# Fuente_v1.net
KiCad netlist of a schematic drawn in EAGLE
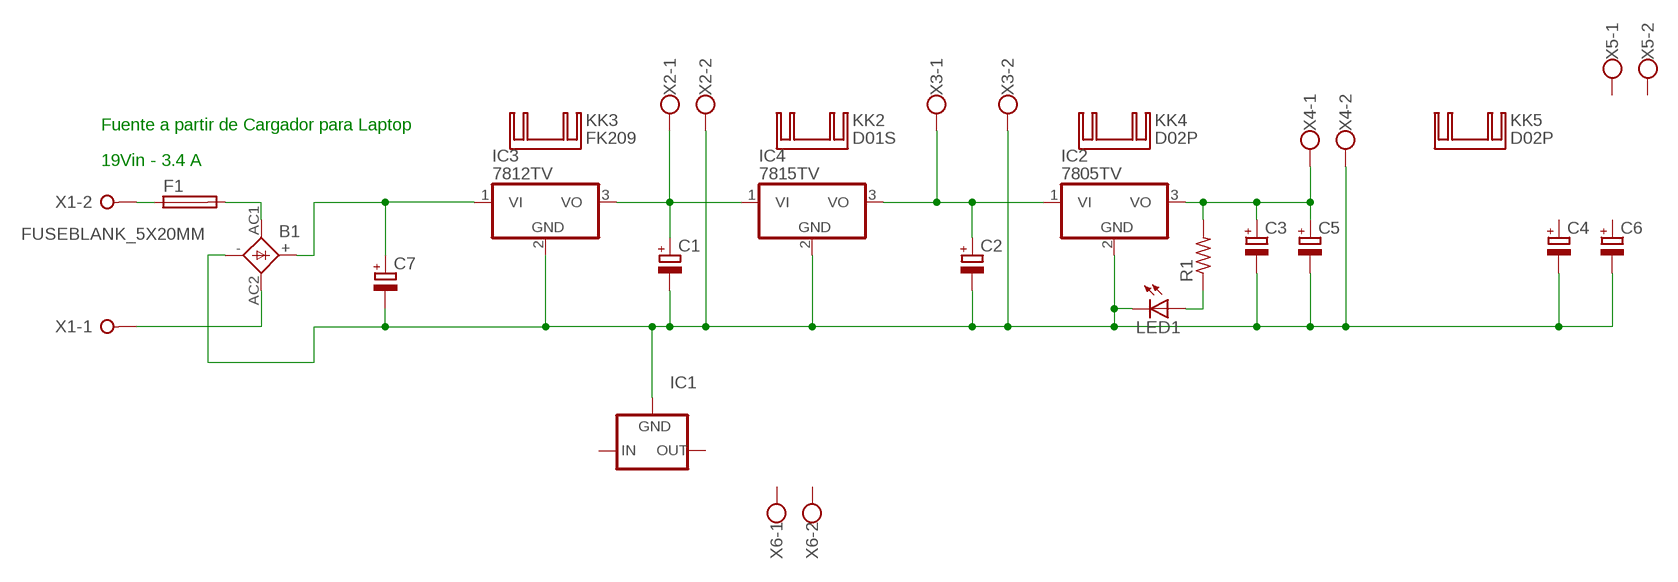
[diagram p0: schematic, sheet 1]

(export (version "E")
  (design (tool "Eeschema 10.0.6"))
  (components
    (comp (ref "B1")
      (value "FBM")
      (footprint "eagle-import:FBM")
      (libsource (lib "eagle-import") (part "FBM"))
    )
    (comp (ref "C1")
      (value "CPOL-EUE2.5-7")
      (footprint "eagle-import:E2,5-7")
      (libsource (lib "eagle-import") (part "CPOL-EUE2.5-7"))
    )
    (comp (ref "C2")
      (value "CPOL-EUE2.5-7")
      (footprint "eagle-import:E2,5-7")
      (libsource (lib "eagle-import") (part "CPOL-EUE2.5-7"))
    )
    (comp (ref "C3")
      (value "CPOL-EUE2.5-7")
      (footprint "eagle-import:E2,5-7")
      (libsource (lib "eagle-import") (part "CPOL-EUE2.5-7"))
    )
    (comp (ref "C4")
      (value "CPOL-EUE2.5-6")
      (footprint "eagle-import:E2,5-6")
      (libsource (lib "eagle-import") (part "CPOL-EUE2.5-6"))
    )
    (comp (ref "C5")
      (value "CPOL-EUE2.5-6")
      (footprint "eagle-import:E2,5-6")
      (libsource (lib "eagle-import") (part "CPOL-EUE2.5-6"))
    )
    (comp (ref "C6")
      (value "CPOL-EUE2.5-6")
      (footprint "eagle-import:E2,5-6")
      (libsource (lib "eagle-import") (part "CPOL-EUE2.5-6"))
    )
    (comp (ref "C7")
      (value "CPOL-EUE2.5-7")
      (footprint "eagle-import:E2,5-7")
      (libsource (lib "eagle-import") (part "CPOL-EUE2.5-7"))
    )
    (comp (ref "F1")
      (value "FUSEBLANK_5X20MM")
      (footprint "eagle-import:FUSE_HOLDER_5X20MM")
      (libsource (lib "eagle-import") (part "FUSEBLANK_5X20MM"))
    )
    (comp (ref "IC1")
      (value "79XX-TO3")
      (footprint "eagle-import:TO3-79")
      (libsource (lib "eagle-import") (part "79XX-TO3"))
    )
    (comp (ref "IC2")
      (value "7805TV")
      (footprint "eagle-import:TO220V")
      (libsource (lib "eagle-import") (part "78TV05"))
    )
    (comp (ref "IC3")
      (value "7812TV")
      (footprint "eagle-import:TO220V")
      (libsource (lib "eagle-import") (part "78TV12"))
    )
    (comp (ref "IC4")
      (value "7815TV")
      (footprint "eagle-import:TO220V")
      (libsource (lib "eagle-import") (part "78TV15"))
    )
    (comp (ref "KK2")
      (value "D01S")
      (footprint "eagle-import:D01S")
      (libsource (lib "eagle-import") (part "D01S"))
    )
    (comp (ref "KK3")
      (value "FK209")
      (footprint "eagle-import:FK209")
      (libsource (lib "eagle-import") (part "FK209"))
    )
    (comp (ref "KK4")
      (value "D02P")
      (footprint "eagle-import:D02PA")
      (libsource (lib "eagle-import") (part "D02P"))
    )
    (comp (ref "KK5")
      (value "D02P")
      (footprint "eagle-import:D02PA")
      (libsource (lib "eagle-import") (part "D02P"))
    )
    (comp (ref "LED1")
      (value "LED5MM")
      (footprint "eagle-import:LED5MM")
      (libsource (lib "eagle-import") (part "LED5MM"))
    )
    (comp (ref "R1")
      (value "R-US_0204/7")
      (footprint "eagle-import:0204_7")
      (libsource (lib "eagle-import") (part "R-US_0204/7"))
    )
    (comp (ref "X1")
      (value "W237-02P")
      (footprint "eagle-import:W237-132")
      (libsource (lib "eagle-import") (part "W237-02P"))
    )
    (comp (ref "X2")
      (value "W237-102")
      (footprint "eagle-import:W237-102")
      (fields (field (name "MPN") "237-102"))
      (libsource (lib "eagle-import") (part "W237-102"))
    )
    (comp (ref "X3")
      (value "W237-102")
      (footprint "eagle-import:W237-102")
      (fields (field (name "MPN") "237-102"))
      (libsource (lib "eagle-import") (part "W237-102"))
    )
    (comp (ref "X4")
      (value "W237-102")
      (footprint "eagle-import:W237-102")
      (fields (field (name "MPN") "237-102"))
      (libsource (lib "eagle-import") (part "W237-102"))
    )
    (comp (ref "X5")
      (value "W237-102")
      (footprint "eagle-import:W237-102")
      (fields (field (name "MPN") "237-102"))
      (libsource (lib "eagle-import") (part "W237-102"))
    )
    (comp (ref "X6")
      (value "W237-102")
      (footprint "eagle-import:W237-102")
      (fields (field (name "MPN") "237-102"))
      (libsource (lib "eagle-import") (part "W237-102"))
    )
  )
  (nets
    (net (code "1") (name "Net-(B1-PadAC1)") (class "Default")
      (node (ref "B1") (pin "AC1") (pinfunction "AC1_AC1") (pintype "passive"))
      (node (ref "F1") (pin "2") (pinfunction "2_2") (pintype "passive"))
    )
    (net (code "2") (name "Net-(IC1-GND)") (class "Default")
      (node (ref "B1") (pin "-") (pinfunction "-_-") (pintype "passive"))
      (node (ref "C1") (pin "-") (pinfunction "-_-") (pintype "passive"))
      (node (ref "C2") (pin "-") (pinfunction "-_-") (pintype "passive"))
      (node (ref "C3") (pin "-") (pinfunction "-_-") (pintype "passive"))
      (node (ref "C4") (pin "-") (pinfunction "-_-") (pintype "passive"))
      (node (ref "C5") (pin "-") (pinfunction "-_-") (pintype "passive"))
      (node (ref "C6") (pin "-") (pinfunction "-_-") (pintype "passive"))
      (node (ref "C7") (pin "-") (pinfunction "-_-") (pintype "passive"))
      (node (ref "IC1") (pin "2") (pinfunction "GND_2") (pintype "input"))
      (node (ref "IC2") (pin "2") (pinfunction "GND_2") (pintype "passive"))
      (node (ref "IC3") (pin "2") (pinfunction "GND_2") (pintype "passive"))
      (node (ref "IC4") (pin "2") (pinfunction "GND_2") (pintype "passive"))
      (node (ref "LED1") (pin "K") (pinfunction "C_K") (pintype "passive"))
      (node (ref "X2") (pin "2") (pinfunction "KL_2") (pintype "passive"))
      (node (ref "X3") (pin "2") (pinfunction "KL_2") (pintype "passive"))
      (node (ref "X4") (pin "2") (pinfunction "KL_2") (pintype "passive"))
    )
    (net (code "3") (name "Net-(IC2-VI)") (class "Default")
      (node (ref "C2") (pin "+") (pinfunction "+_+") (pintype "passive"))
      (node (ref "IC2") (pin "1") (pinfunction "VI_1") (pintype "input"))
      (node (ref "IC4") (pin "3") (pinfunction "VO_3") (pintype "passive"))
      (node (ref "X3") (pin "1") (pinfunction "KL_1") (pintype "passive"))
    )
    (net (code "4") (name "Net-(IC2-VO)") (class "Default")
      (node (ref "C3") (pin "+") (pinfunction "+_+") (pintype "passive"))
      (node (ref "C5") (pin "+") (pinfunction "+_+") (pintype "passive"))
      (node (ref "IC2") (pin "3") (pinfunction "VO_3") (pintype "passive"))
      (node (ref "R1") (pin "2") (pinfunction "2_2") (pintype "passive"))
      (node (ref "X4") (pin "1") (pinfunction "KL_1") (pintype "passive"))
    )
    (net (code "5") (name "Net-(IC3-VI)") (class "Default")
      (node (ref "B1") (pin "+") (pinfunction "+_+") (pintype "passive"))
      (node (ref "C7") (pin "+") (pinfunction "+_+") (pintype "passive"))
      (node (ref "IC3") (pin "1") (pinfunction "VI_1") (pintype "input"))
    )
    (net (code "6") (name "Net-(IC3-VO)") (class "Default")
      (node (ref "C1") (pin "+") (pinfunction "+_+") (pintype "passive"))
      (node (ref "IC3") (pin "3") (pinfunction "VO_3") (pintype "passive"))
      (node (ref "IC4") (pin "1") (pinfunction "VI_1") (pintype "input"))
      (node (ref "X2") (pin "1") (pinfunction "KL_1") (pintype "passive"))
    )
    (net (code "7") (name "Net-(LED1-PadA)") (class "Default")
      (node (ref "LED1") (pin "A") (pinfunction "A_A") (pintype "passive"))
      (node (ref "R1") (pin "1") (pinfunction "1_1") (pintype "passive"))
    )
    (net (code "8") (name "Net-(X1A-KL)") (class "Default")
      (node (ref "B1") (pin "AC2") (pinfunction "AC2_AC2") (pintype "passive"))
      (node (ref "X1") (pin "1") (pinfunction "KL_1") (pintype "passive"))
    )
    (net (code "9") (name "Net-(X1B-KL)") (class "Default")
      (node (ref "F1") (pin "1") (pinfunction "1_1") (pintype "passive"))
      (node (ref "X1") (pin "2") (pinfunction "KL_2") (pintype "passive"))
    )
    (net (code "10") (name "unconnected-(C4-Pad+)") (class "Default")
      (node (ref "C4") (pin "+") (pinfunction "+_+") (pintype "passive"))
    )
    (net (code "11") (name "unconnected-(C6-Pad+)") (class "Default")
      (node (ref "C6") (pin "+") (pinfunction "+_+") (pintype "passive"))
    )
    (net (code "12") (name "unconnected-(IC1-IN-Pad3)") (class "Default")
      (node (ref "IC1") (pin "3") (pinfunction "IN_3") (pintype "input"))
    )
    (net (code "13") (name "unconnected-(IC1-OUT-Pad1)") (class "Default")
      (node (ref "IC1") (pin "1") (pinfunction "OUT_1") (pintype "passive"))
    )
    (net (code "14") (name "unconnected-(X5A-KL-Pad1)") (class "Default")
      (node (ref "X5") (pin "1") (pinfunction "KL_1") (pintype "passive"))
    )
    (net (code "15") (name "unconnected-(X5B-KL-Pad2)") (class "Default")
      (node (ref "X5") (pin "2") (pinfunction "KL_2") (pintype "passive"))
    )
    (net (code "16") (name "unconnected-(X6A-KL-Pad1)") (class "Default")
      (node (ref "X6") (pin "1") (pinfunction "KL_1") (pintype "passive"))
    )
    (net (code "17") (name "unconnected-(X6B-KL-Pad2)") (class "Default")
      (node (ref "X6") (pin "2") (pinfunction "KL_2") (pintype "passive"))
    )
  )
)
